# display_device.net
KiCad netlist of a schematic drawn in EAGLE
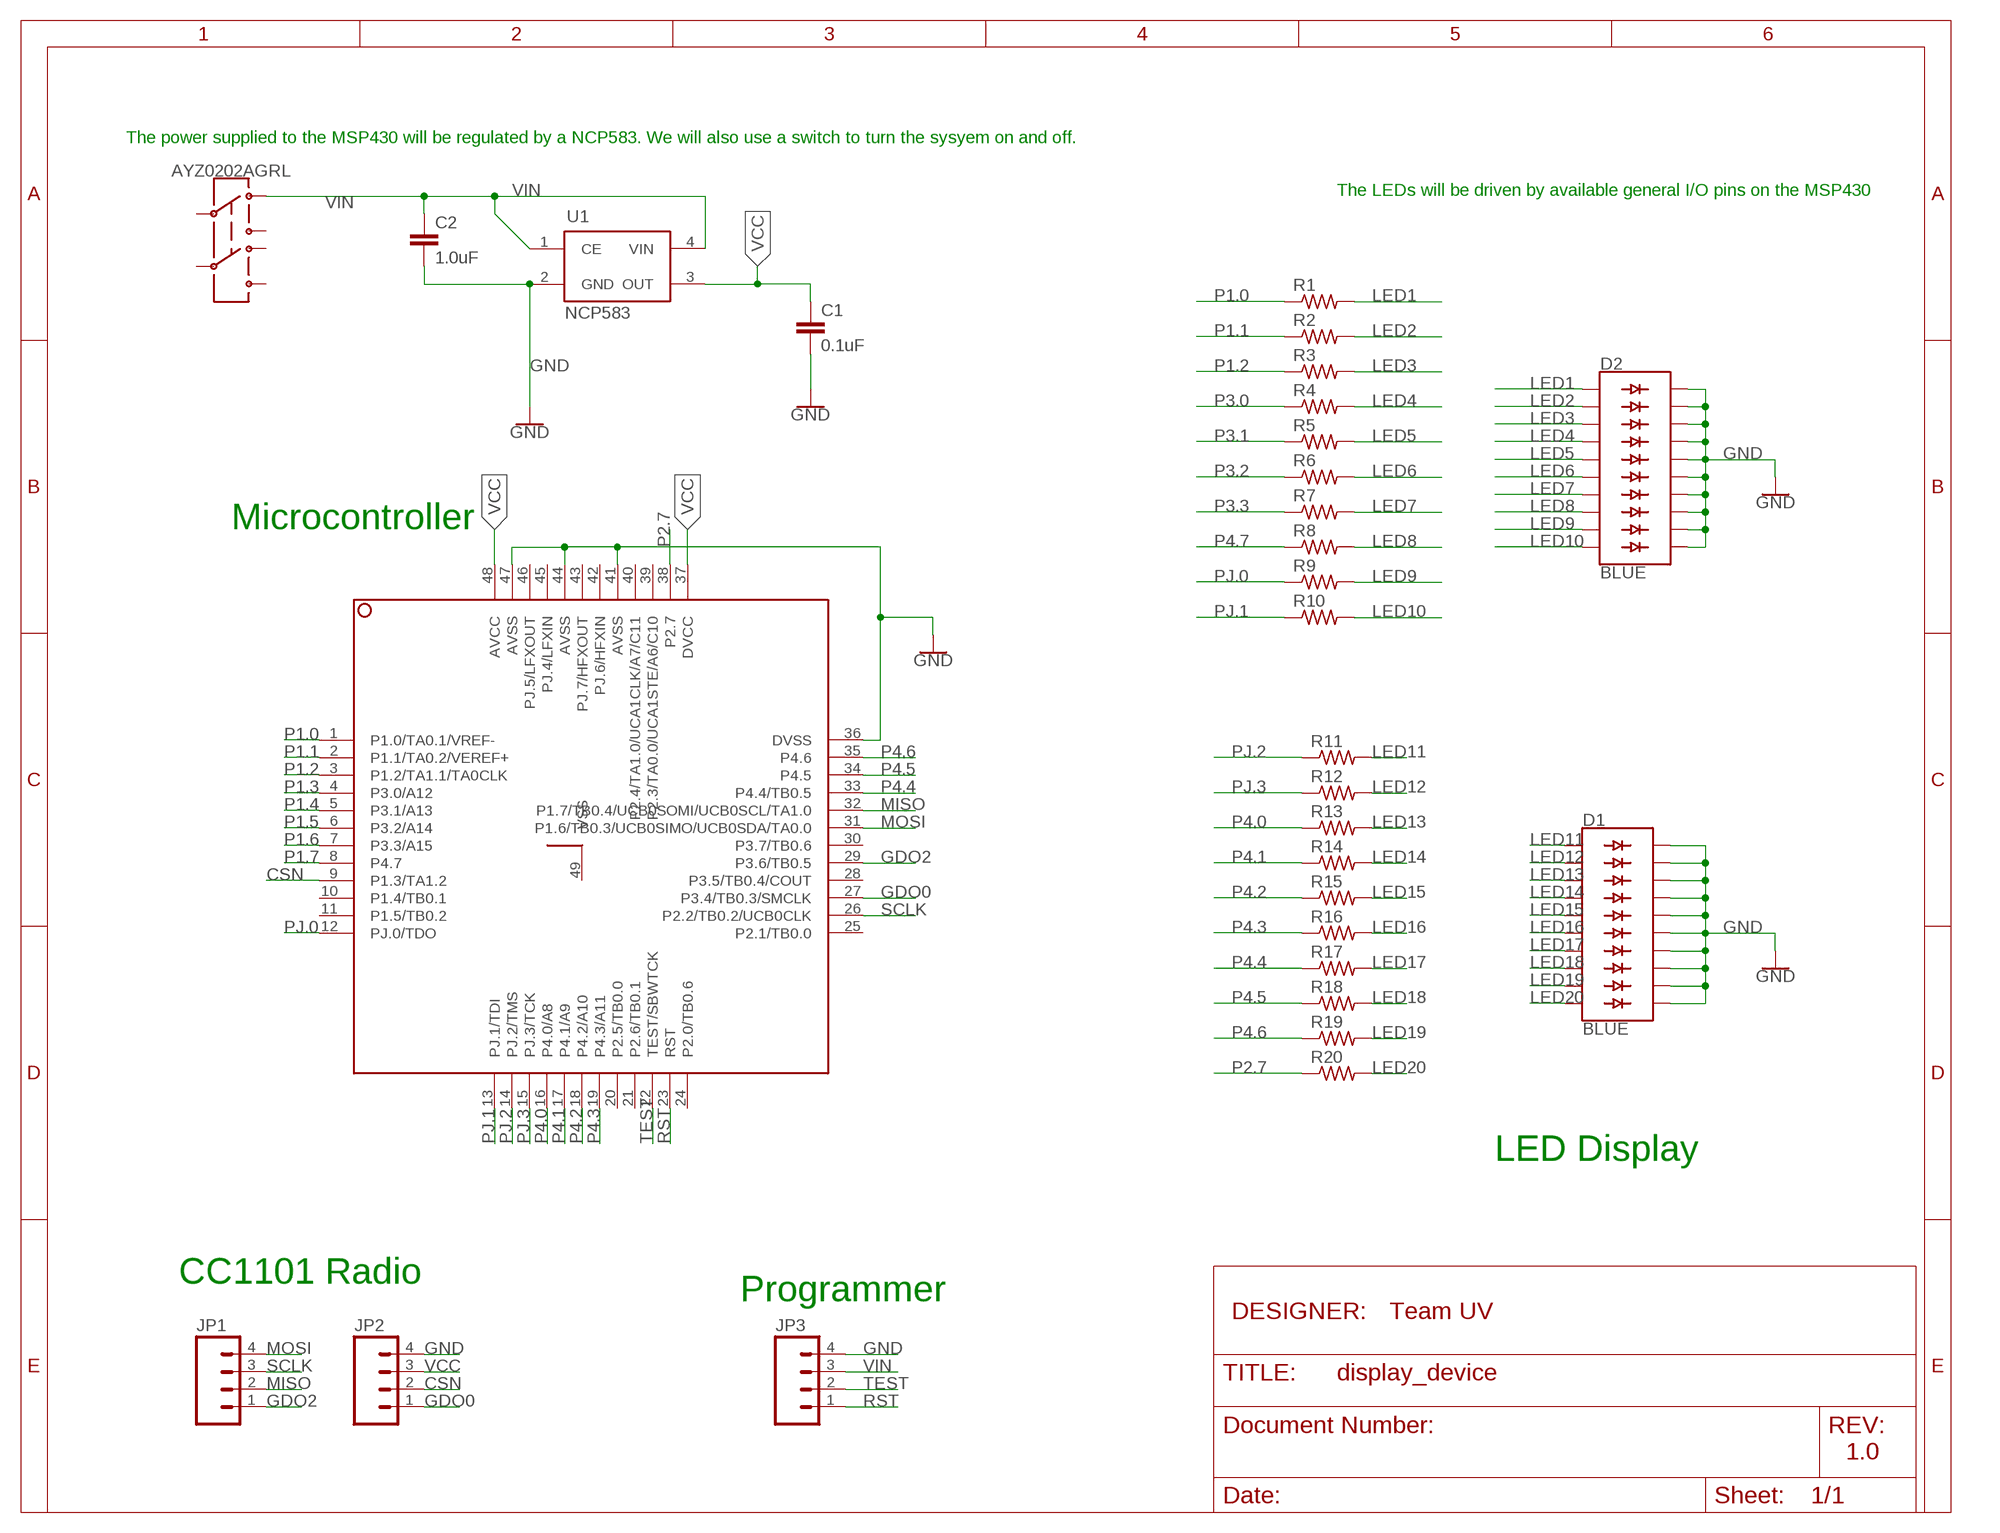
[diagram p0: schematic, sheet 1]

(export (version "E")
  (design (tool "Eeschema 10.0.6"))
  (components
    (comp (ref "AYZ0202AGRL")
      (value "SWITCH-DPDT-SMD-AYZ0202")
      (footprint "eagle-import:SWITCH_DPDT_SMD_AYZ0202")
      (libsource (lib "eagle-import") (part "SWITCH-DPDT-SMD-AYZ0202"))
    )
    (comp (ref "C1")
      (value "0.1uF")
      (footprint "eagle-import:0805")
      (libsource (lib "eagle-import") (part "1.0UF-0805-25V-(+80/-20%)"))
    )
    (comp (ref "C2")
      (value "1.0uF")
      (footprint "eagle-import:0805")
      (libsource (lib "eagle-import") (part "1.0UF-0805-25V-(+80/-20%)"))
    )
    (comp (ref "D1")
      (value "BLUE")
      (footprint "eagle-import:LED_BARGRAPH_10")
      (libsource (lib "eagle-import") (part "LED_BARGRAPH_10BLUE"))
    )
    (comp (ref "D2")
      (value "BLUE")
      (footprint "eagle-import:LED_BARGRAPH_10")
      (libsource (lib "eagle-import") (part "LED_BARGRAPH_10BLUE"))
    )
    (comp (ref "JP1")
      (value "M04PTH")
      (footprint "eagle-import:1X04")
      (libsource (lib "eagle-import") (part "M04PTH"))
    )
    (comp (ref "JP2")
      (value "M04PTH")
      (footprint "eagle-import:1X04")
      (libsource (lib "eagle-import") (part "M04PTH"))
    )
    (comp (ref "JP3")
      (value "M04PTH")
      (footprint "eagle-import:1X04")
      (libsource (lib "eagle-import") (part "M04PTH"))
    )
    (comp (ref "R1")
      (value "R-US_R0805")
      (footprint "eagle-import:R0805")
      (libsource (lib "eagle-import") (part "R-US_R0805"))
    )
    (comp (ref "R2")
      (value "R-US_R0805")
      (footprint "eagle-import:R0805")
      (libsource (lib "eagle-import") (part "R-US_R0805"))
    )
    (comp (ref "R3")
      (value "R-US_R0805")
      (footprint "eagle-import:R0805")
      (libsource (lib "eagle-import") (part "R-US_R0805"))
    )
    (comp (ref "R4")
      (value "R-US_R0805")
      (footprint "eagle-import:R0805")
      (libsource (lib "eagle-import") (part "R-US_R0805"))
    )
    (comp (ref "R5")
      (value "R-US_R0805")
      (footprint "eagle-import:R0805")
      (libsource (lib "eagle-import") (part "R-US_R0805"))
    )
    (comp (ref "R6")
      (value "R-US_R0805")
      (footprint "eagle-import:R0805")
      (libsource (lib "eagle-import") (part "R-US_R0805"))
    )
    (comp (ref "R7")
      (value "R-US_R0805")
      (footprint "eagle-import:R0805")
      (libsource (lib "eagle-import") (part "R-US_R0805"))
    )
    (comp (ref "R8")
      (value "R-US_R0805")
      (footprint "eagle-import:R0805")
      (libsource (lib "eagle-import") (part "R-US_R0805"))
    )
    (comp (ref "R9")
      (value "R-US_R0805")
      (footprint "eagle-import:R0805")
      (libsource (lib "eagle-import") (part "R-US_R0805"))
    )
    (comp (ref "R10")
      (value "R-US_R0805")
      (footprint "eagle-import:R0805")
      (libsource (lib "eagle-import") (part "R-US_R0805"))
    )
    (comp (ref "R11")
      (value "R-US_R0805")
      (footprint "eagle-import:R0805")
      (libsource (lib "eagle-import") (part "R-US_R0805"))
    )
    (comp (ref "R12")
      (value "R-US_R0805")
      (footprint "eagle-import:R0805")
      (libsource (lib "eagle-import") (part "R-US_R0805"))
    )
    (comp (ref "R13")
      (value "R-US_R0805")
      (footprint "eagle-import:R0805")
      (libsource (lib "eagle-import") (part "R-US_R0805"))
    )
    (comp (ref "R14")
      (value "R-US_R0805")
      (footprint "eagle-import:R0805")
      (libsource (lib "eagle-import") (part "R-US_R0805"))
    )
    (comp (ref "R15")
      (value "R-US_R0805")
      (footprint "eagle-import:R0805")
      (libsource (lib "eagle-import") (part "R-US_R0805"))
    )
    (comp (ref "R16")
      (value "R-US_R0805")
      (footprint "eagle-import:R0805")
      (libsource (lib "eagle-import") (part "R-US_R0805"))
    )
    (comp (ref "R17")
      (value "R-US_R0805")
      (footprint "eagle-import:R0805")
      (libsource (lib "eagle-import") (part "R-US_R0805"))
    )
    (comp (ref "R18")
      (value "R-US_R0805")
      (footprint "eagle-import:R0805")
      (libsource (lib "eagle-import") (part "R-US_R0805"))
    )
    (comp (ref "R19")
      (value "R-US_R0805")
      (footprint "eagle-import:R0805")
      (libsource (lib "eagle-import") (part "R-US_R0805"))
    )
    (comp (ref "R20")
      (value "R-US_R0805")
      (footprint "eagle-import:R0805")
      (libsource (lib "eagle-import") (part "R-US_R0805"))
    )
    (comp (ref "U1")
      (value "NCP583")
      (footprint "eagle-import:SC82-AB_1PRIMARY")
      (libsource (lib "eagle-import") (part "NCP583"))
    )
    (comp (ref "U2")
      (value "MSP430FR5969_RGZ_48")
      (footprint "eagle-import:RGZ48_4P1X4P1")
      (fields (field (name "MANUFACTURER_PART_NUMBER") "msp430fr5969_rgz_48"))
      (libsource (lib "eagle-import") (part "MSP430FR5969_RGZ_48"))
    )
  )
  (nets
    (net (code "1") (name "/CSN") (class "Default")
      (node (ref "JP2") (pin "2") (pinfunction "2_2") (pintype "passive"))
      (node (ref "U2") (pin "9") (pinfunction "P1.3/TA1.2_9") (pintype "bidirectional"))
    )
    (net (code "2") (name "/GDO0") (class "Default")
      (node (ref "JP2") (pin "1") (pinfunction "1_1") (pintype "passive"))
      (node (ref "U2") (pin "27") (pinfunction "P3.4/TB0.3/SMCLK_27") (pintype "bidirectional"))
    )
    (net (code "3") (name "/GDO2") (class "Default")
      (node (ref "JP1") (pin "1") (pinfunction "1_1") (pintype "passive"))
      (node (ref "U2") (pin "29") (pinfunction "P3.6/TB0.5_29") (pintype "bidirectional"))
    )
    (net (code "4") (name "/LED1") (class "Default")
      (node (ref "D2") (pin "1") (pinfunction "A_1") (pintype "passive"))
      (node (ref "R1") (pin "2") (pinfunction "2_2") (pintype "passive"))
    )
    (net (code "5") (name "/LED2") (class "Default")
      (node (ref "D2") (pin "2") (pinfunction "A1_2") (pintype "passive"))
      (node (ref "R2") (pin "2") (pinfunction "2_2") (pintype "passive"))
    )
    (net (code "6") (name "/LED3") (class "Default")
      (node (ref "D2") (pin "3") (pinfunction "A2_3") (pintype "passive"))
      (node (ref "R3") (pin "2") (pinfunction "2_2") (pintype "passive"))
    )
    (net (code "7") (name "/LED4") (class "Default")
      (node (ref "D2") (pin "4") (pinfunction "A3_4") (pintype "passive"))
      (node (ref "R4") (pin "2") (pinfunction "2_2") (pintype "passive"))
    )
    (net (code "8") (name "/LED5") (class "Default")
      (node (ref "D2") (pin "5") (pinfunction "A4_5") (pintype "passive"))
      (node (ref "R5") (pin "2") (pinfunction "2_2") (pintype "passive"))
    )
    (net (code "9") (name "/LED6") (class "Default")
      (node (ref "D2") (pin "6") (pinfunction "A5_6") (pintype "passive"))
      (node (ref "R6") (pin "2") (pinfunction "2_2") (pintype "passive"))
    )
    (net (code "10") (name "/LED7") (class "Default")
      (node (ref "D2") (pin "7") (pinfunction "A6_7") (pintype "passive"))
      (node (ref "R7") (pin "2") (pinfunction "2_2") (pintype "passive"))
    )
    (net (code "11") (name "/LED8") (class "Default")
      (node (ref "D2") (pin "8") (pinfunction "A7_8") (pintype "passive"))
      (node (ref "R8") (pin "2") (pinfunction "2_2") (pintype "passive"))
    )
    (net (code "12") (name "/LED9") (class "Default")
      (node (ref "D2") (pin "9") (pinfunction "A8_9") (pintype "passive"))
      (node (ref "R9") (pin "2") (pinfunction "2_2") (pintype "passive"))
    )
    (net (code "13") (name "/LED10") (class "Default")
      (node (ref "D2") (pin "10") (pinfunction "A9_10") (pintype "passive"))
      (node (ref "R10") (pin "2") (pinfunction "2_2") (pintype "passive"))
    )
    (net (code "14") (name "/LED11") (class "Default")
      (node (ref "D1") (pin "1") (pinfunction "A_1") (pintype "passive"))
      (node (ref "R11") (pin "2") (pinfunction "2_2") (pintype "passive"))
    )
    (net (code "15") (name "/LED12") (class "Default")
      (node (ref "D1") (pin "2") (pinfunction "A1_2") (pintype "passive"))
      (node (ref "R12") (pin "2") (pinfunction "2_2") (pintype "passive"))
    )
    (net (code "16") (name "/LED13") (class "Default")
      (node (ref "D1") (pin "3") (pinfunction "A2_3") (pintype "passive"))
      (node (ref "R13") (pin "2") (pinfunction "2_2") (pintype "passive"))
    )
    (net (code "17") (name "/LED14") (class "Default")
      (node (ref "D1") (pin "4") (pinfunction "A3_4") (pintype "passive"))
      (node (ref "R14") (pin "2") (pinfunction "2_2") (pintype "passive"))
    )
    (net (code "18") (name "/LED15") (class "Default")
      (node (ref "D1") (pin "5") (pinfunction "A4_5") (pintype "passive"))
      (node (ref "R15") (pin "2") (pinfunction "2_2") (pintype "passive"))
    )
    (net (code "19") (name "/LED16") (class "Default")
      (node (ref "D1") (pin "6") (pinfunction "A5_6") (pintype "passive"))
      (node (ref "R16") (pin "2") (pinfunction "2_2") (pintype "passive"))
    )
    (net (code "20") (name "/LED17") (class "Default")
      (node (ref "D1") (pin "7") (pinfunction "A6_7") (pintype "passive"))
      (node (ref "R17") (pin "2") (pinfunction "2_2") (pintype "passive"))
    )
    (net (code "21") (name "/LED18") (class "Default")
      (node (ref "D1") (pin "8") (pinfunction "A7_8") (pintype "passive"))
      (node (ref "R18") (pin "2") (pinfunction "2_2") (pintype "passive"))
    )
    (net (code "22") (name "/LED19") (class "Default")
      (node (ref "D1") (pin "9") (pinfunction "A8_9") (pintype "passive"))
      (node (ref "R19") (pin "2") (pinfunction "2_2") (pintype "passive"))
    )
    (net (code "23") (name "/LED20") (class "Default")
      (node (ref "D1") (pin "10") (pinfunction "A9_10") (pintype "passive"))
      (node (ref "R20") (pin "2") (pinfunction "2_2") (pintype "passive"))
    )
    (net (code "24") (name "/MISO") (class "Default")
      (node (ref "JP1") (pin "2") (pinfunction "2_2") (pintype "passive"))
      (node (ref "U2") (pin "32") (pinfunction "P1.7/TB0.4/UCB0SOMI/UCB0SCL/TA1.0_32") (pintype "bidirectional"))
    )
    (net (code "25") (name "/MOSI") (class "Default")
      (node (ref "JP1") (pin "4") (pinfunction "4_4") (pintype "passive"))
      (node (ref "U2") (pin "31") (pinfunction "P1.6/TB0.3/UCB0SIMO/UCB0SDA/TA0.0_31") (pintype "bidirectional"))
    )
    (net (code "26") (name "/P1.0") (class "Default")
      (node (ref "R1") (pin "1") (pinfunction "1_1") (pintype "passive"))
      (node (ref "U2") (pin "1") (pinfunction "P1.0/TA0.1/VREF-_1") (pintype "bidirectional"))
    )
    (net (code "27") (name "/P1.1") (class "Default")
      (node (ref "R2") (pin "1") (pinfunction "1_1") (pintype "passive"))
      (node (ref "U2") (pin "2") (pinfunction "P1.1/TA0.2/VEREF+_2") (pintype "bidirectional"))
    )
    (net (code "28") (name "/P1.2") (class "Default")
      (node (ref "R3") (pin "1") (pinfunction "1_1") (pintype "passive"))
      (node (ref "U2") (pin "3") (pinfunction "P1.2/TA1.1/TA0CLK_3") (pintype "bidirectional"))
    )
    (net (code "29") (name "/P1.3") (class "Default")
      (node (ref "U2") (pin "4") (pinfunction "P3.0/A12_4") (pintype "bidirectional"))
    )
    (net (code "30") (name "/P1.4") (class "Default")
      (node (ref "U2") (pin "5") (pinfunction "P3.1/A13_5") (pintype "bidirectional"))
    )
    (net (code "31") (name "/P1.5") (class "Default")
      (node (ref "U2") (pin "6") (pinfunction "P3.2/A14_6") (pintype "bidirectional"))
    )
    (net (code "32") (name "/P1.6") (class "Default")
      (node (ref "U2") (pin "7") (pinfunction "P3.3/A15_7") (pintype "bidirectional"))
    )
    (net (code "33") (name "/P1.7") (class "Default")
      (node (ref "U2") (pin "8") (pinfunction "P4.7_8") (pintype "bidirectional"))
    )
    (net (code "34") (name "/P2.7") (class "Default")
      (node (ref "R20") (pin "1") (pinfunction "1_1") (pintype "passive"))
      (node (ref "U2") (pin "38") (pinfunction "P2.7_38") (pintype "bidirectional"))
    )
    (net (code "35") (name "/P3.0") (class "Default")
      (node (ref "R4") (pin "1") (pinfunction "1_1") (pintype "passive"))
    )
    (net (code "36") (name "/P3.1") (class "Default")
      (node (ref "R5") (pin "1") (pinfunction "1_1") (pintype "passive"))
    )
    (net (code "37") (name "/P3.2") (class "Default")
      (node (ref "R6") (pin "1") (pinfunction "1_1") (pintype "passive"))
    )
    (net (code "38") (name "/P3.3") (class "Default")
      (node (ref "R7") (pin "1") (pinfunction "1_1") (pintype "passive"))
    )
    (net (code "39") (name "/P4.0") (class "Default")
      (node (ref "R13") (pin "1") (pinfunction "1_1") (pintype "passive"))
      (node (ref "U2") (pin "16") (pinfunction "P4.0/A8_16") (pintype "bidirectional"))
    )
    (net (code "40") (name "/P4.1") (class "Default")
      (node (ref "R14") (pin "1") (pinfunction "1_1") (pintype "passive"))
      (node (ref "U2") (pin "17") (pinfunction "P4.1/A9_17") (pintype "bidirectional"))
    )
    (net (code "41") (name "/P4.2") (class "Default")
      (node (ref "R15") (pin "1") (pinfunction "1_1") (pintype "passive"))
      (node (ref "U2") (pin "18") (pinfunction "P4.2/A10_18") (pintype "bidirectional"))
    )
    (net (code "42") (name "/P4.3") (class "Default")
      (node (ref "R16") (pin "1") (pinfunction "1_1") (pintype "passive"))
      (node (ref "U2") (pin "19") (pinfunction "P4.3/A11_19") (pintype "bidirectional"))
    )
    (net (code "43") (name "/P4.4") (class "Default")
      (node (ref "R17") (pin "1") (pinfunction "1_1") (pintype "passive"))
      (node (ref "U2") (pin "33") (pinfunction "P4.4/TB0.5_33") (pintype "bidirectional"))
    )
    (net (code "44") (name "/P4.5") (class "Default")
      (node (ref "R18") (pin "1") (pinfunction "1_1") (pintype "passive"))
      (node (ref "U2") (pin "34") (pinfunction "P4.5_34") (pintype "bidirectional"))
    )
    (net (code "45") (name "/P4.6") (class "Default")
      (node (ref "R19") (pin "1") (pinfunction "1_1") (pintype "passive"))
      (node (ref "U2") (pin "35") (pinfunction "P4.6_35") (pintype "bidirectional"))
    )
    (net (code "46") (name "/P4.7") (class "Default")
      (node (ref "R8") (pin "1") (pinfunction "1_1") (pintype "passive"))
    )
    (net (code "47") (name "/PJ.0") (class "Default")
      (node (ref "R9") (pin "1") (pinfunction "1_1") (pintype "passive"))
      (node (ref "U2") (pin "12") (pinfunction "PJ.0/TDO_12") (pintype "bidirectional"))
    )
    (net (code "48") (name "/PJ.1") (class "Default")
      (node (ref "R10") (pin "1") (pinfunction "1_1") (pintype "passive"))
      (node (ref "U2") (pin "13") (pinfunction "PJ.1/TDI_13") (pintype "bidirectional"))
    )
    (net (code "49") (name "/PJ.2") (class "Default")
      (node (ref "R11") (pin "1") (pinfunction "1_1") (pintype "passive"))
      (node (ref "U2") (pin "14") (pinfunction "PJ.2/TMS_14") (pintype "bidirectional"))
    )
    (net (code "50") (name "/PJ.3") (class "Default")
      (node (ref "R12") (pin "1") (pinfunction "1_1") (pintype "passive"))
      (node (ref "U2") (pin "15") (pinfunction "PJ.3/TCK_15") (pintype "bidirectional"))
    )
    (net (code "51") (name "/RST") (class "Default")
      (node (ref "JP3") (pin "1") (pinfunction "1_1") (pintype "passive"))
      (node (ref "U2") (pin "23") (pinfunction "RST_23") (pintype "bidirectional"))
    )
    (net (code "52") (name "/SCLK") (class "Default")
      (node (ref "JP1") (pin "3") (pinfunction "3_3") (pintype "passive"))
      (node (ref "U2") (pin "26") (pinfunction "P2.2/TB0.2/UCB0CLK_26") (pintype "bidirectional"))
    )
    (net (code "53") (name "/TEST") (class "Default")
      (node (ref "JP3") (pin "2") (pinfunction "2_2") (pintype "passive"))
      (node (ref "U2") (pin "22") (pinfunction "TEST/SBWTCK_22") (pintype "bidirectional"))
    )
    (net (code "54") (name "/VIN") (class "Default")
      (node (ref "AYZ0202AGRL") (pin "1") (pinfunction "1_1") (pintype "bidirectional"))
      (node (ref "C2") (pin "1") (pinfunction "1_1") (pintype "passive"))
      (node (ref "JP3") (pin "3") (pinfunction "3_3") (pintype "passive"))
      (node (ref "U1") (pin "1") (pinfunction "CE_1") (pintype "bidirectional"))
      (node (ref "U1") (pin "4") (pinfunction "VIN_4") (pintype "bidirectional"))
    )
    (net (code "55") (name "GND") (class "Default")
      (node (ref "C1") (pin "2") (pinfunction "2_2") (pintype "passive"))
      (node (ref "C2") (pin "2") (pinfunction "2_2") (pintype "passive"))
      (node (ref "D1") (pin "11") (pinfunction "C9_11") (pintype "passive"))
      (node (ref "D1") (pin "12") (pinfunction "C8_12") (pintype "passive"))
      (node (ref "D1") (pin "13") (pinfunction "C7_13") (pintype "passive"))
      (node (ref "D1") (pin "14") (pinfunction "C6_14") (pintype "passive"))
      (node (ref "D1") (pin "15") (pinfunction "C5_15") (pintype "passive"))
      (node (ref "D1") (pin "16") (pinfunction "C4_16") (pintype "passive"))
      (node (ref "D1") (pin "17") (pinfunction "C3_17") (pintype "passive"))
      (node (ref "D1") (pin "18") (pinfunction "C2_18") (pintype "passive"))
      (node (ref "D1") (pin "19") (pinfunction "C1_19") (pintype "passive"))
      (node (ref "D1") (pin "20") (pinfunction "C_20") (pintype "passive"))
      (node (ref "D2") (pin "11") (pinfunction "C9_11") (pintype "passive"))
      (node (ref "D2") (pin "12") (pinfunction "C8_12") (pintype "passive"))
      (node (ref "D2") (pin "13") (pinfunction "C7_13") (pintype "passive"))
      (node (ref "D2") (pin "14") (pinfunction "C6_14") (pintype "passive"))
      (node (ref "D2") (pin "15") (pinfunction "C5_15") (pintype "passive"))
      (node (ref "D2") (pin "16") (pinfunction "C4_16") (pintype "passive"))
      (node (ref "D2") (pin "17") (pinfunction "C3_17") (pintype "passive"))
      (node (ref "D2") (pin "18") (pinfunction "C2_18") (pintype "passive"))
      (node (ref "D2") (pin "19") (pinfunction "C1_19") (pintype "passive"))
      (node (ref "D2") (pin "20") (pinfunction "C_20") (pintype "passive"))
      (node (ref "JP2") (pin "4") (pinfunction "4_4") (pintype "passive"))
      (node (ref "JP3") (pin "4") (pinfunction "4_4") (pintype "passive"))
      (node (ref "U1") (pin "2") (pinfunction "GND_2") (pintype "bidirectional"))
      (node (ref "U2") (pin "36") (pinfunction "DVSS_36") (pintype "bidirectional"))
      (node (ref "U2") (pin "41") (pinfunction "AVSS_41") (pintype "bidirectional"))
      (node (ref "U2") (pin "44") (pinfunction "AVSS_44") (pintype "bidirectional"))
      (node (ref "U2") (pin "47") (pinfunction "AVSS_47") (pintype "bidirectional"))
    )
    (net (code "56") (name "VCC") (class "Default")
      (node (ref "C1") (pin "1") (pinfunction "1_1") (pintype "passive"))
      (node (ref "JP2") (pin "3") (pinfunction "3_3") (pintype "passive"))
      (node (ref "U1") (pin "3") (pinfunction "OUT_3") (pintype "bidirectional"))
      (node (ref "U2") (pin "37") (pinfunction "DVCC_37") (pintype "bidirectional"))
      (node (ref "U2") (pin "48") (pinfunction "AVCC_48") (pintype "bidirectional"))
    )
    (net (code "57") (name "unconnected-(AYZ0202AGRL-Pad2)") (class "Default")
      (node (ref "AYZ0202AGRL") (pin "2") (pinfunction "2_2") (pintype "bidirectional"))
    )
    (net (code "58") (name "unconnected-(AYZ0202AGRL-Pad3)") (class "Default")
      (node (ref "AYZ0202AGRL") (pin "3") (pinfunction "3_3") (pintype "bidirectional"))
    )
    (net (code "59") (name "unconnected-(AYZ0202AGRL-Pad4)") (class "Default")
      (node (ref "AYZ0202AGRL") (pin "4") (pinfunction "4_4") (pintype "bidirectional"))
    )
    (net (code "60") (name "unconnected-(AYZ0202AGRL-Pad5)") (class "Default")
      (node (ref "AYZ0202AGRL") (pin "5") (pinfunction "5_5") (pintype "bidirectional"))
    )
    (net (code "61") (name "unconnected-(AYZ0202AGRL-Pad6)") (class "Default")
      (node (ref "AYZ0202AGRL") (pin "6") (pinfunction "6_6") (pintype "bidirectional"))
    )
    (net (code "62") (name "unconnected-(U2-P1.4{slash}TB0.1-Pad10)") (class "Default")
      (node (ref "U2") (pin "10") (pinfunction "P1.4/TB0.1_10") (pintype "bidirectional"))
    )
    (net (code "63") (name "unconnected-(U2-P1.5{slash}TB0.2-Pad11)") (class "Default")
      (node (ref "U2") (pin "11") (pinfunction "P1.5/TB0.2_11") (pintype "bidirectional"))
    )
    (net (code "64") (name "unconnected-(U2-P2.0{slash}TB0.6-Pad24)") (class "Default")
      (node (ref "U2") (pin "24") (pinfunction "P2.0/TB0.6_24") (pintype "bidirectional"))
    )
    (net (code "65") (name "unconnected-(U2-P2.1{slash}TB0.0-Pad25)") (class "Default")
      (node (ref "U2") (pin "25") (pinfunction "P2.1/TB0.0_25") (pintype "bidirectional"))
    )
    (net (code "66") (name "unconnected-(U2-P2.3{slash}TA0.0{slash}UCA1STE{slash}A6{slash}C10-Pad39)") (class "Default")
      (node (ref "U2") (pin "39") (pinfunction "P2.3/TA0.0/UCA1STE/A6/C10_39") (pintype "bidirectional"))
    )
    (net (code "67") (name "unconnected-(U2-P2.4{slash}TA1.0{slash}UCA1CLK{slash}A7{slash}C11-Pad40)") (class "Default")
      (node (ref "U2") (pin "40") (pinfunction "P2.4/TA1.0/UCA1CLK/A7/C11_40") (pintype "bidirectional"))
    )
    (net (code "68") (name "unconnected-(U2-P2.5{slash}TB0.0-Pad20)") (class "Default")
      (node (ref "U2") (pin "20") (pinfunction "P2.5/TB0.0_20") (pintype "bidirectional"))
    )
    (net (code "69") (name "unconnected-(U2-P2.6{slash}TB0.1-Pad21)") (class "Default")
      (node (ref "U2") (pin "21") (pinfunction "P2.6/TB0.1_21") (pintype "bidirectional"))
    )
    (net (code "70") (name "unconnected-(U2-P3.5{slash}TB0.4{slash}COUT-Pad28)") (class "Default")
      (node (ref "U2") (pin "28") (pinfunction "P3.5/TB0.4/COUT_28") (pintype "bidirectional"))
    )
    (net (code "71") (name "unconnected-(U2-P3.7{slash}TB0.6-Pad30)") (class "Default")
      (node (ref "U2") (pin "30") (pinfunction "P3.7/TB0.6_30") (pintype "bidirectional"))
    )
    (net (code "72") (name "unconnected-(U2-PJ.4{slash}LFXIN-Pad45)") (class "Default")
      (node (ref "U2") (pin "45") (pinfunction "PJ.4/LFXIN_45") (pintype "bidirectional"))
    )
    (net (code "73") (name "unconnected-(U2-PJ.5{slash}LFXOUT-Pad46)") (class "Default")
      (node (ref "U2") (pin "46") (pinfunction "PJ.5/LFXOUT_46") (pintype "bidirectional"))
    )
    (net (code "74") (name "unconnected-(U2-PJ.6{slash}HFXIN-Pad42)") (class "Default")
      (node (ref "U2") (pin "42") (pinfunction "PJ.6/HFXIN_42") (pintype "bidirectional"))
    )
    (net (code "75") (name "unconnected-(U2-PJ.7{slash}HFXOUT-Pad43)") (class "Default")
      (node (ref "U2") (pin "43") (pinfunction "PJ.7/HFXOUT_43") (pintype "bidirectional"))
    )
    (net (code "76") (name "unconnected-(U2-VSS-Pad49)") (class "Default")
      (node (ref "U2") (pin "49") (pinfunction "VSS_49") (pintype "bidirectional"))
    )
  )
)
